# main.net
KiCad netlist of a schematic drawn in Altium Designer
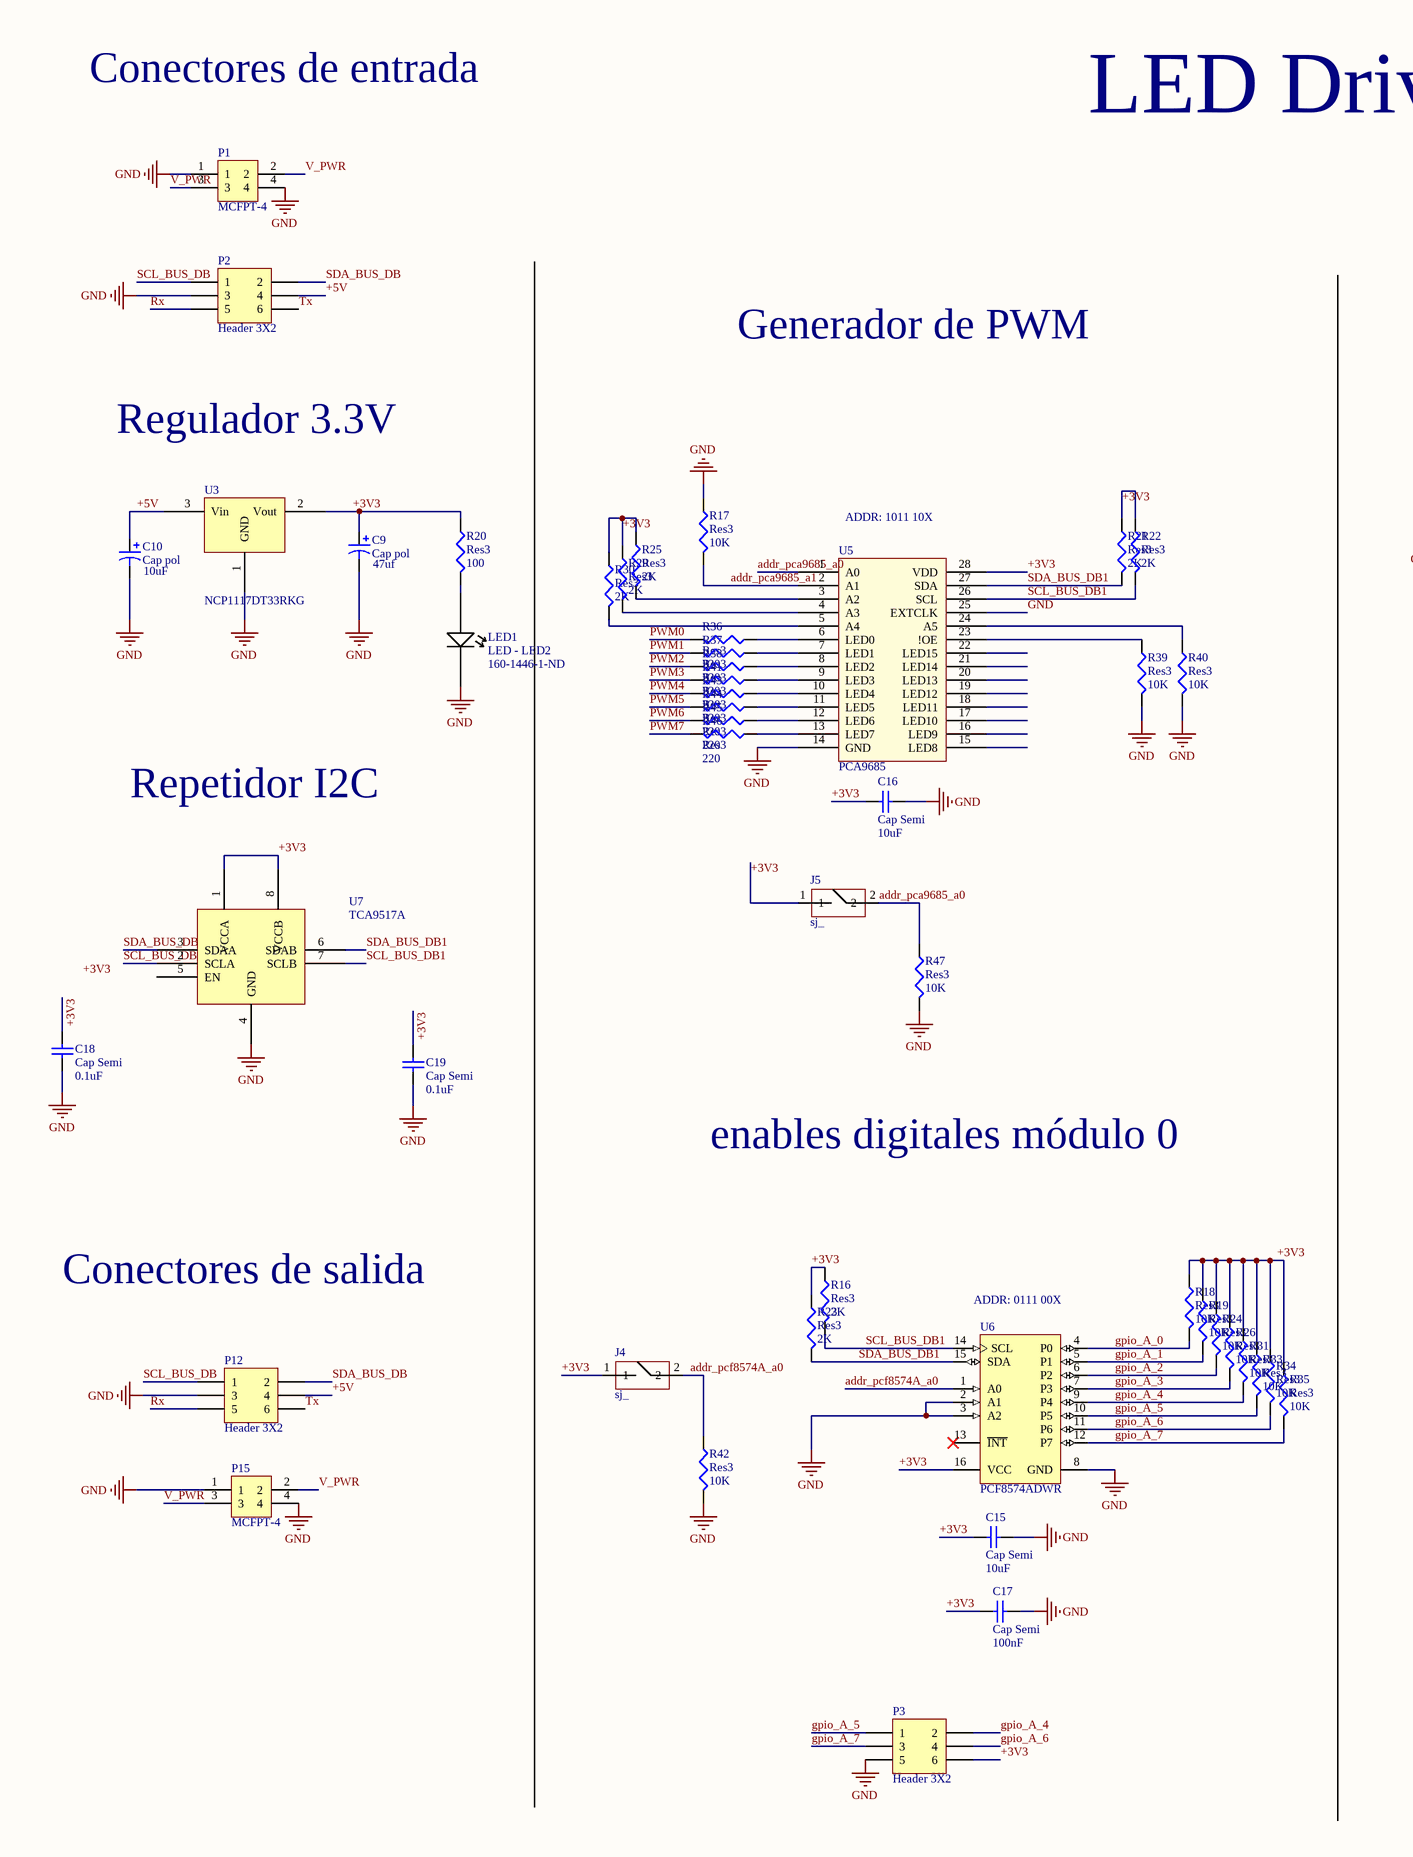
[diagram p0: main.SchDoc, left]
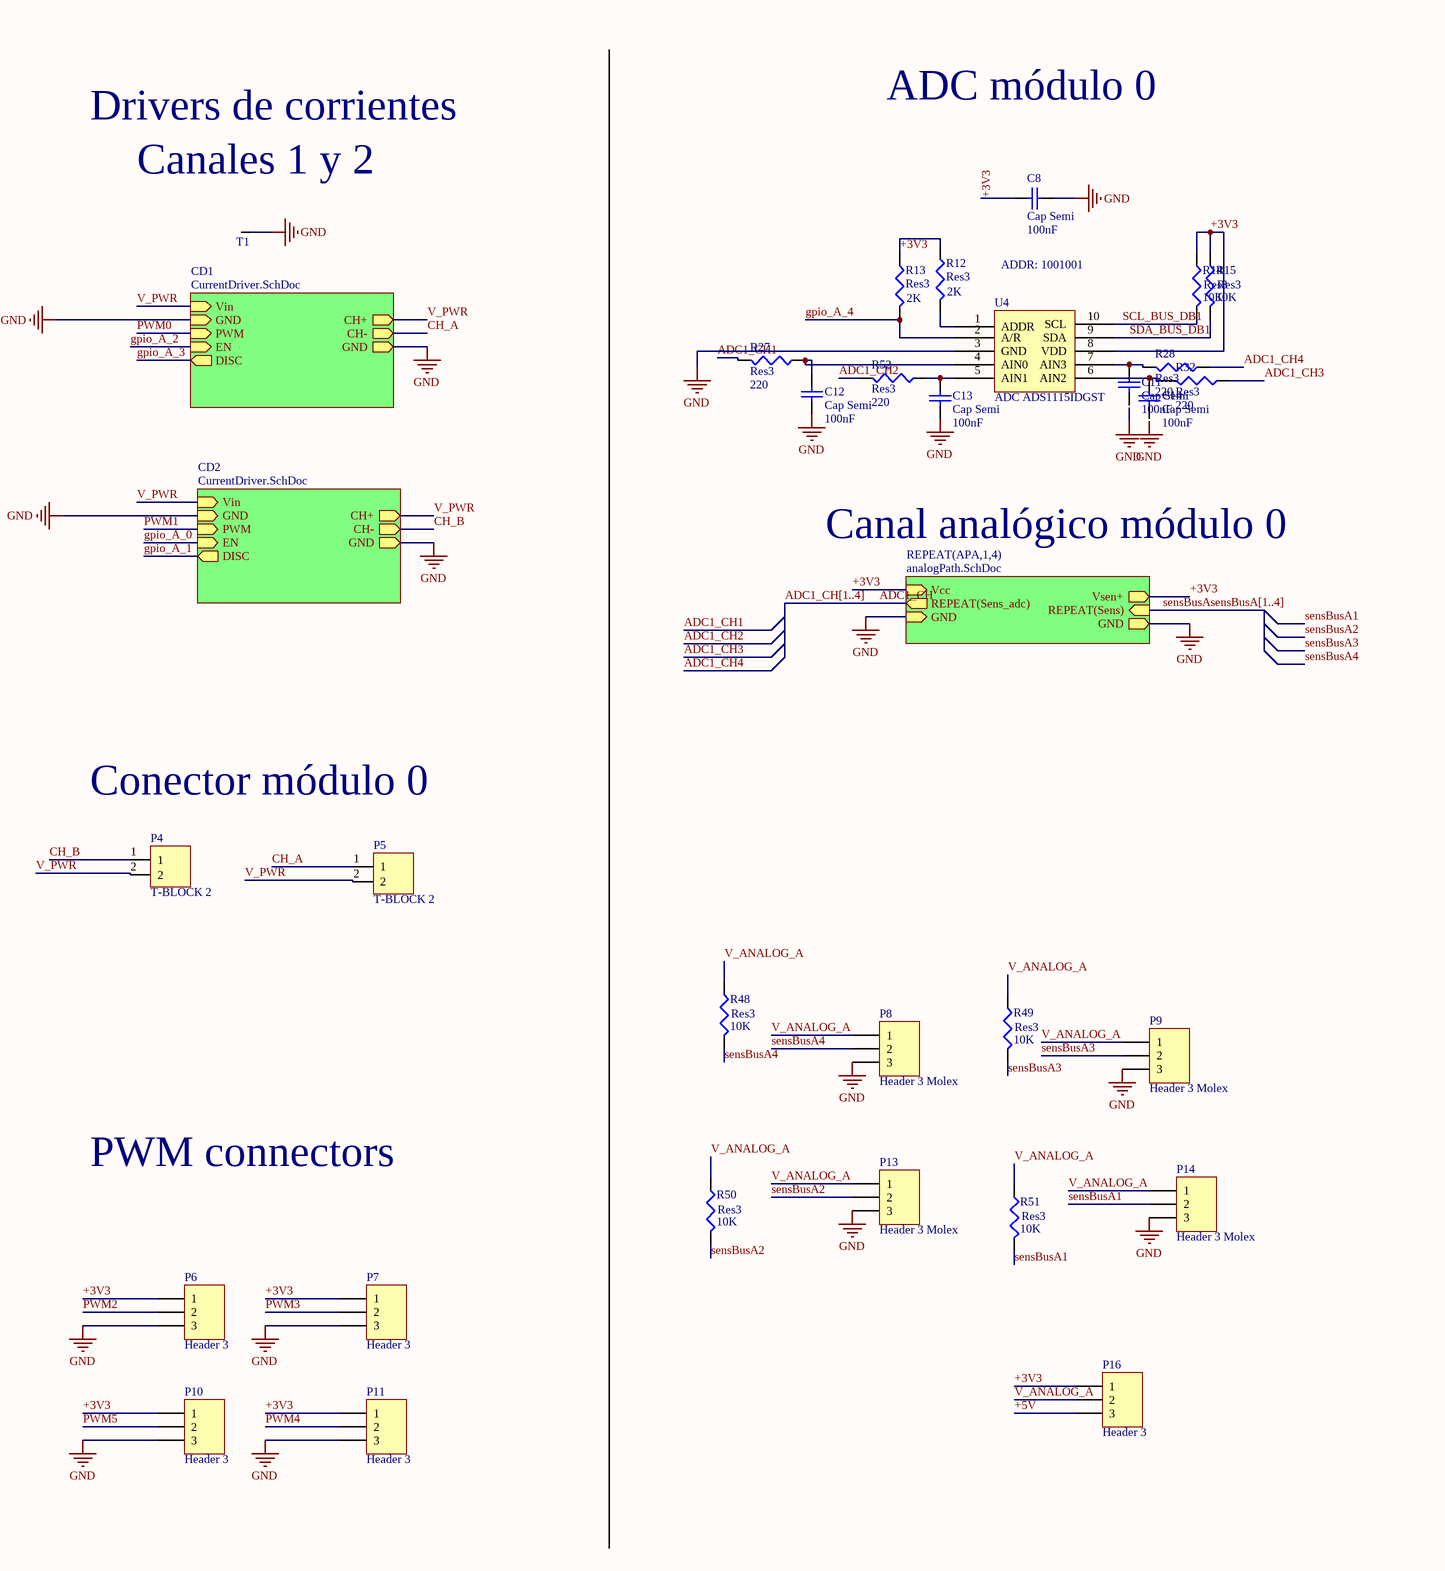
[diagram p1: main.SchDoc, right]

(export (version "E")
  (design (tool "Eeschema 10.0.6"))
  (components
    (comp (ref "C8")
      (value "Cap Semi")
      (footprint "1608[0603]")
      (description "Capacitor (Semiconductor SIM Model)")
      (fields (field (name "ALTIUM_VALUE") "100nF") (field (name "PUBLISHER") "Altium Limited"))
      (libsource (lib "Miscellaneous Devices") (part "Cap Semi"))
    )
    (comp (ref "C9")
      (value "Cap pol")
      (footprint "CAPEA-5.30x5.30")
      (description "Cap Generic")
      (fields (field (name "ALTIUM_VALUE") "47uf"))
      (libsource (lib "ASI-LIB") (part "Cap pol generic"))
    )
    (comp (ref "C10")
      (value "Cap pol")
      (footprint "CAPEA-4.30x4.30")
      (description "Cap Generic")
      (fields (field (name "ALTIUM_VALUE") "10uF"))
      (libsource (lib "ASI-LIB") (part "Cap pol generic"))
    )
    (comp (ref "C11")
      (value "Cap Semi")
      (footprint "1608[0603]")
      (description "Capacitor (Semiconductor SIM Model)")
      (fields (field (name "ALTIUM_VALUE") "100nF") (field (name "PUBLISHER") "Altium Limited"))
      (libsource (lib "Miscellaneous Devices") (part "Cap Semi"))
    )
    (comp (ref "C12")
      (value "Cap Semi")
      (footprint "1608[0603]")
      (description "Capacitor (Semiconductor SIM Model)")
      (fields (field (name "ALTIUM_VALUE") "100nF") (field (name "PUBLISHER") "Altium Limited"))
      (libsource (lib "Miscellaneous Devices") (part "Cap Semi"))
    )
    (comp (ref "C13")
      (value "Cap Semi")
      (footprint "1608[0603]")
      (description "Capacitor (Semiconductor SIM Model)")
      (fields (field (name "ALTIUM_VALUE") "100nF") (field (name "PUBLISHER") "Altium Limited"))
      (libsource (lib "Miscellaneous Devices") (part "Cap Semi"))
    )
    (comp (ref "C14")
      (value "Cap Semi")
      (footprint "1608[0603]")
      (description "Capacitor (Semiconductor SIM Model)")
      (fields (field (name "ALTIUM_VALUE") "100nF") (field (name "PUBLISHER") "Altium Limited"))
      (libsource (lib "Miscellaneous Devices") (part "Cap Semi"))
    )
    (comp (ref "C15")
      (value "Cap Semi")
      (footprint "1608[0603]")
      (description "Capacitor (Semiconductor SIM Model)")
      (fields (field (name "ALTIUM_VALUE") "10uF") (field (name "PUBLISHER") "Altium Limited"))
      (libsource (lib "Miscellaneous Devices") (part "Cap Semi"))
    )
    (comp (ref "C16")
      (value "Cap Semi")
      (footprint "1608[0603]")
      (description "Capacitor (Semiconductor SIM Model)")
      (fields (field (name "ALTIUM_VALUE") "10uF") (field (name "PUBLISHER") "Altium Limited"))
      (libsource (lib "Miscellaneous Devices") (part "Cap Semi"))
    )
    (comp (ref "C17")
      (value "Cap Semi")
      (footprint "1608[0603]")
      (description "Capacitor (Semiconductor SIM Model)")
      (fields (field (name "ALTIUM_VALUE") "100nF") (field (name "PUBLISHER") "Altium Limited"))
      (libsource (lib "Miscellaneous Devices") (part "Cap Semi"))
    )
    (comp (ref "C18")
      (value "Cap Semi")
      (footprint "1608[0603]")
      (description "Capacitor (Semiconductor SIM Model)")
      (fields (field (name "ALTIUM_VALUE") "0.1uF") (field (name "PUBLISHER") "Altium Limited"))
      (libsource (lib "Miscellaneous Devices") (part "Cap Semi"))
    )
    (comp (ref "C19")
      (value "Cap Semi")
      (footprint "1608[0603]")
      (description "Capacitor (Semiconductor SIM Model)")
      (fields (field (name "ALTIUM_VALUE") "0.1uF") (field (name "PUBLISHER") "Altium Limited"))
      (libsource (lib "Miscellaneous Devices") (part "Cap Semi"))
    )
    (comp (ref "J4")
      (value "sj_")
      (footprint "JUMPER_NET_TIE")
      (description "solder jumper generic")
      (libsource (lib "ASI-LIB") (part "Jumper"))
    )
    (comp (ref "J5")
      (value "sj_")
      (footprint "JUMPER_NET_TIE")
      (description "solder jumper generic")
      (libsource (lib "ASI-LIB") (part "Jumper"))
    )
    (comp (ref "LED1")
      (value "LED - LED2")
      (footprint "LED")
      (fields (field (name "SUPPLIER PART NUMBER 1") "160-1446-1-ND"))
      (libsource (lib "ASI-LIB") (part "LED - LED2"))
    )
    (comp (ref "P1")
      (value "MCFPT-4")
      (footprint "MCFPT-4-VERT")
      (description "POWER CONN")
      (libsource (lib "ASI-LIB") (part "CON - MCFPT-4"))
    )
    (comp (ref "P2")
      (value "Header 3X2")
      (footprint "HDR2X3")
      (description "Header, 3-Pin, Dual row")
      (fields (field (name "PUBLISHER") "Altium Limited"))
      (libsource (lib "Miscellaneous Connectors") (part "Header 3X2"))
    )
    (comp (ref "P3")
      (value "Header 3X2")
      (footprint "HDR2X3")
      (description "Header, 3-Pin, Dual row")
      (fields (field (name "PUBLISHER") "Altium Limited"))
      (libsource (lib "Miscellaneous Connectors") (part "Header 3X2"))
    )
    (comp (ref "P4")
      (value "T-BLOCK 2")
      (footprint "T-BLOCK_2_3MM")
      (description "TE Connectivity Buchanan Series 3.5mm Pitch Straight, PCB Terminal Block, Through Hole, 2 Way")
      (libsource (lib "ASI-LIB") (part "T-BLOCK_2_3MM"))
    )
    (comp (ref "P5")
      (value "T-BLOCK 2")
      (footprint "T-BLOCK_2_3MM")
      (description "TE Connectivity Buchanan Series 3.5mm Pitch Straight, PCB Terminal Block, Through Hole, 2 Way")
      (libsource (lib "ASI-LIB") (part "T-BLOCK_2_3MM"))
    )
    (comp (ref "P6")
      (value "Header 3")
      (footprint "HDR1X3")
      (description "Header, 3-Pin")
      (fields (field (name "PUBLISHER") "Altium Limited"))
      (libsource (lib "Miscellaneous Connectors") (part "Header 3"))
    )
    (comp (ref "P7")
      (value "Header 3")
      (footprint "HDR1X3")
      (description "Header, 3-Pin")
      (fields (field (name "PUBLISHER") "Altium Limited"))
      (libsource (lib "Miscellaneous Connectors") (part "Header 3"))
    )
    (comp (ref "P8")
      (value "Header 3 Molex")
      (footprint "HDR1X3")
      (description "Header, 3-Pin")
      (fields (field (name "GENERIC PART NUMBER") "22272031") (field (name "PUBLISHER") "Altium Limited"))
      (libsource (lib "ASI-LIB") (part "Header 3 Molex"))
    )
    (comp (ref "P9")
      (value "Header 3 Molex")
      (footprint "HDR1X3")
      (description "Header, 3-Pin")
      (fields (field (name "GENERIC PART NUMBER") "22272031") (field (name "PUBLISHER") "Altium Limited"))
      (libsource (lib "ASI-LIB") (part "Header 3 Molex"))
    )
    (comp (ref "P10")
      (value "Header 3")
      (footprint "HDR1X3")
      (description "Header, 3-Pin")
      (fields (field (name "PUBLISHER") "Altium Limited"))
      (libsource (lib "Miscellaneous Connectors") (part "Header 3"))
    )
    (comp (ref "P11")
      (value "Header 3")
      (footprint "HDR1X3")
      (description "Header, 3-Pin")
      (fields (field (name "PUBLISHER") "Altium Limited"))
      (libsource (lib "Miscellaneous Connectors") (part "Header 3"))
    )
    (comp (ref "P12")
      (value "Header 3X2")
      (footprint "HDR2X3")
      (description "Header, 3-Pin, Dual row")
      (fields (field (name "PUBLISHER") "Altium Limited"))
      (libsource (lib "Miscellaneous Connectors") (part "Header 3X2"))
    )
    (comp (ref "P13")
      (value "Header 3 Molex")
      (footprint "HDR1X3")
      (description "Header, 3-Pin")
      (fields (field (name "GENERIC PART NUMBER") "22272031") (field (name "PUBLISHER") "Altium Limited"))
      (libsource (lib "ASI-LIB") (part "Header 3 Molex"))
    )
    (comp (ref "P14")
      (value "Header 3 Molex")
      (footprint "HDR1X3")
      (description "Header, 3-Pin")
      (fields (field (name "GENERIC PART NUMBER") "22272031") (field (name "PUBLISHER") "Altium Limited"))
      (libsource (lib "ASI-LIB") (part "Header 3 Molex"))
    )
    (comp (ref "P15")
      (value "MCFPT-4")
      (footprint "MCFPT-4-VERT")
      (description "POWER CONN")
      (libsource (lib "ASI-LIB") (part "CON - MCFPT-4"))
    )
    (comp (ref "P16")
      (value "Header 3")
      (footprint "HDR1X3")
      (description "Header, 3-Pin")
      (fields (field (name "PUBLISHER") "Altium Limited"))
      (libsource (lib "Miscellaneous Connectors") (part "Header 3"))
    )
    (comp (ref "R12")
      (value "Res3")
      (footprint "J1-0603")
      (description "Resistor")
      (fields (field (name "ALTIUM_VALUE") "2K") (field (name "PUBLISHER") "Altium Limited"))
      (libsource (lib "Miscellaneous Devices") (part "Res3"))
    )
    (comp (ref "R13")
      (value "Res3")
      (footprint "J1-0603")
      (description "Resistor")
      (fields (field (name "ALTIUM_VALUE") "2K") (field (name "PUBLISHER") "Altium Limited"))
      (libsource (lib "Miscellaneous Devices") (part "Res3"))
    )
    (comp (ref "R14")
      (value "Res3")
      (footprint "J1-0603")
      (description "Resistor")
      (fields (field (name "ALTIUM_VALUE") "10K") (field (name "PUBLISHER") "Altium Limited"))
      (libsource (lib "Miscellaneous Devices") (part "Res3"))
    )
    (comp (ref "R15")
      (value "Res3")
      (footprint "J1-0603")
      (description "Resistor")
      (fields (field (name "ALTIUM_VALUE") "10K") (field (name "PUBLISHER") "Altium Limited"))
      (libsource (lib "Miscellaneous Devices") (part "Res3"))
    )
    (comp (ref "R16")
      (value "Res3")
      (footprint "J1-0603")
      (description "Resistor")
      (fields (field (name "ALTIUM_VALUE") "2K") (field (name "PUBLISHER") "Altium Limited"))
      (libsource (lib "Miscellaneous Devices") (part "Res3"))
    )
    (comp (ref "R17")
      (value "Res3")
      (footprint "J1-0603")
      (description "Resistor")
      (fields (field (name "ALTIUM_VALUE") "10K") (field (name "PUBLISHER") "Altium Limited"))
      (libsource (lib "Miscellaneous Devices") (part "Res3"))
    )
    (comp (ref "R18")
      (value "Res3")
      (footprint "J1-0603")
      (description "Resistor")
      (fields (field (name "ALTIUM_VALUE") "10K") (field (name "PUBLISHER") "Altium Limited"))
      (libsource (lib "Miscellaneous Devices") (part "Res3"))
    )
    (comp (ref "R19")
      (value "Res3")
      (footprint "J1-0603")
      (description "Resistor")
      (fields (field (name "ALTIUM_VALUE") "10K") (field (name "PUBLISHER") "Altium Limited"))
      (libsource (lib "Miscellaneous Devices") (part "Res3"))
    )
    (comp (ref "R20")
      (value "Res3")
      (footprint "J1-0603")
      (description "Resistor")
      (fields (field (name "ALTIUM_VALUE") "100") (field (name "PUBLISHER") "Altium Limited"))
      (libsource (lib "Miscellaneous Devices") (part "Res3"))
    )
    (comp (ref "R21")
      (value "Res3")
      (footprint "J1-0603")
      (description "Resistor")
      (fields (field (name "ALTIUM_VALUE") "2K") (field (name "PUBLISHER") "Altium Limited"))
      (libsource (lib "Miscellaneous Devices") (part "Res3"))
    )
    (comp (ref "R22")
      (value "Res3")
      (footprint "J1-0603")
      (description "Resistor")
      (fields (field (name "ALTIUM_VALUE") "2K") (field (name "PUBLISHER") "Altium Limited"))
      (libsource (lib "Miscellaneous Devices") (part "Res3"))
    )
    (comp (ref "R23")
      (value "Res3")
      (footprint "J1-0603")
      (description "Resistor")
      (fields (field (name "ALTIUM_VALUE") "2K") (field (name "PUBLISHER") "Altium Limited"))
      (libsource (lib "Miscellaneous Devices") (part "Res3"))
    )
    (comp (ref "R24")
      (value "Res3")
      (footprint "J1-0603")
      (description "Resistor")
      (fields (field (name "ALTIUM_VALUE") "10K") (field (name "PUBLISHER") "Altium Limited"))
      (libsource (lib "Miscellaneous Devices") (part "Res3"))
    )
    (comp (ref "R25")
      (value "Res3")
      (footprint "J1-0603")
      (description "Resistor")
      (fields (field (name "ALTIUM_VALUE") "2K") (field (name "PUBLISHER") "Altium Limited"))
      (libsource (lib "Miscellaneous Devices") (part "Res3"))
    )
    (comp (ref "R26")
      (value "Res3")
      (footprint "J1-0603")
      (description "Resistor")
      (fields (field (name "ALTIUM_VALUE") "10K") (field (name "PUBLISHER") "Altium Limited"))
      (libsource (lib "Miscellaneous Devices") (part "Res3"))
    )
    (comp (ref "R27")
      (value "Res3")
      (footprint "J1-0603")
      (description "Resistor")
      (fields (field (name "ALTIUM_VALUE") "220") (field (name "PUBLISHER") "Altium Limited"))
      (libsource (lib "Miscellaneous Devices") (part "Res3"))
    )
    (comp (ref "R28")
      (value "Res3")
      (footprint "J1-0603")
      (description "Resistor")
      (fields (field (name "ALTIUM_VALUE") "220") (field (name "PUBLISHER") "Altium Limited"))
      (libsource (lib "Miscellaneous Devices") (part "Res3"))
    )
    (comp (ref "R29")
      (value "Res3")
      (footprint "J1-0603")
      (description "Resistor")
      (fields (field (name "ALTIUM_VALUE") "2K") (field (name "PUBLISHER") "Altium Limited"))
      (libsource (lib "Miscellaneous Devices") (part "Res3"))
    )
    (comp (ref "R30")
      (value "Res3")
      (footprint "J1-0603")
      (description "Resistor")
      (fields (field (name "ALTIUM_VALUE") "2K") (field (name "PUBLISHER") "Altium Limited"))
      (libsource (lib "Miscellaneous Devices") (part "Res3"))
    )
    (comp (ref "R31")
      (value "Res3")
      (footprint "J1-0603")
      (description "Resistor")
      (fields (field (name "ALTIUM_VALUE") "10K") (field (name "PUBLISHER") "Altium Limited"))
      (libsource (lib "Miscellaneous Devices") (part "Res3"))
    )
    (comp (ref "R32")
      (value "Res3")
      (footprint "J1-0603")
      (description "Resistor")
      (fields (field (name "ALTIUM_VALUE") "220") (field (name "PUBLISHER") "Altium Limited"))
      (libsource (lib "Miscellaneous Devices") (part "Res3"))
    )
    (comp (ref "R33")
      (value "Res3")
      (footprint "J1-0603")
      (description "Resistor")
      (fields (field (name "ALTIUM_VALUE") "10K") (field (name "PUBLISHER") "Altium Limited"))
      (libsource (lib "Miscellaneous Devices") (part "Res3"))
    )
    (comp (ref "R34")
      (value "Res3")
      (footprint "J1-0603")
      (description "Resistor")
      (fields (field (name "ALTIUM_VALUE") "10K") (field (name "PUBLISHER") "Altium Limited"))
      (libsource (lib "Miscellaneous Devices") (part "Res3"))
    )
    (comp (ref "R35")
      (value "Res3")
      (footprint "J1-0603")
      (description "Resistor")
      (fields (field (name "ALTIUM_VALUE") "10K") (field (name "PUBLISHER") "Altium Limited"))
      (libsource (lib "Miscellaneous Devices") (part "Res3"))
    )
    (comp (ref "R36")
      (value "Res3")
      (footprint "J1-0603")
      (description "Resistor")
      (fields (field (name "ALTIUM_VALUE") "220") (field (name "PUBLISHER") "Altium Limited"))
      (libsource (lib "Miscellaneous Devices") (part "Res3"))
    )
    (comp (ref "R37")
      (value "Res3")
      (footprint "J1-0603")
      (description "Resistor")
      (fields (field (name "ALTIUM_VALUE") "220") (field (name "PUBLISHER") "Altium Limited"))
      (libsource (lib "Miscellaneous Devices") (part "Res3"))
    )
    (comp (ref "R38")
      (value "Res3")
      (footprint "J1-0603")
      (description "Resistor")
      (fields (field (name "ALTIUM_VALUE") "220") (field (name "PUBLISHER") "Altium Limited"))
      (libsource (lib "Miscellaneous Devices") (part "Res3"))
    )
    (comp (ref "R39")
      (value "Res3")
      (footprint "J1-0603")
      (description "Resistor")
      (fields (field (name "ALTIUM_VALUE") "10K") (field (name "PUBLISHER") "Altium Limited"))
      (libsource (lib "Miscellaneous Devices") (part "Res3"))
    )
    (comp (ref "R40")
      (value "Res3")
      (footprint "J1-0603")
      (description "Resistor")
      (fields (field (name "ALTIUM_VALUE") "10K") (field (name "PUBLISHER") "Altium Limited"))
      (libsource (lib "Miscellaneous Devices") (part "Res3"))
    )
    (comp (ref "R41")
      (value "Res3")
      (footprint "J1-0603")
      (description "Resistor")
      (fields (field (name "ALTIUM_VALUE") "220") (field (name "PUBLISHER") "Altium Limited"))
      (libsource (lib "Miscellaneous Devices") (part "Res3"))
    )
    (comp (ref "R42")
      (value "Res3")
      (footprint "J1-0603")
      (description "Resistor")
      (fields (field (name "ALTIUM_VALUE") "10K") (field (name "PUBLISHER") "Altium Limited"))
      (libsource (lib "Miscellaneous Devices") (part "Res3"))
    )
    (comp (ref "R43")
      (value "Res3")
      (footprint "J1-0603")
      (description "Resistor")
      (fields (field (name "ALTIUM_VALUE") "220") (field (name "PUBLISHER") "Altium Limited"))
      (libsource (lib "Miscellaneous Devices") (part "Res3"))
    )
    (comp (ref "R44")
      (value "Res3")
      (footprint "J1-0603")
      (description "Resistor")
      (fields (field (name "ALTIUM_VALUE") "220") (field (name "PUBLISHER") "Altium Limited"))
      (libsource (lib "Miscellaneous Devices") (part "Res3"))
    )
    (comp (ref "R45")
      (value "Res3")
      (footprint "J1-0603")
      (description "Resistor")
      (fields (field (name "ALTIUM_VALUE") "220") (field (name "PUBLISHER") "Altium Limited"))
      (libsource (lib "Miscellaneous Devices") (part "Res3"))
    )
    (comp (ref "R46")
      (value "Res3")
      (footprint "J1-0603")
      (description "Resistor")
      (fields (field (name "ALTIUM_VALUE") "220") (field (name "PUBLISHER") "Altium Limited"))
      (libsource (lib "Miscellaneous Devices") (part "Res3"))
    )
    (comp (ref "R47")
      (value "Res3")
      (footprint "J1-0603")
      (description "Resistor")
      (fields (field (name "ALTIUM_VALUE") "10K") (field (name "PUBLISHER") "Altium Limited"))
      (libsource (lib "Miscellaneous Devices") (part "Res3"))
    )
    (comp (ref "R48")
      (value "Res3")
      (footprint "J1-0603")
      (description "Resistor")
      (fields (field (name "ALTIUM_VALUE") "10K") (field (name "PUBLISHER") "Altium Limited"))
      (libsource (lib "Miscellaneous Devices") (part "Res3"))
    )
    (comp (ref "R49")
      (value "Res3")
      (footprint "J1-0603")
      (description "Resistor")
      (fields (field (name "ALTIUM_VALUE") "10K") (field (name "PUBLISHER") "Altium Limited"))
      (libsource (lib "Miscellaneous Devices") (part "Res3"))
    )
    (comp (ref "R50")
      (value "Res3")
      (footprint "J1-0603")
      (description "Resistor")
      (fields (field (name "ALTIUM_VALUE") "10K") (field (name "PUBLISHER") "Altium Limited"))
      (libsource (lib "Miscellaneous Devices") (part "Res3"))
    )
    (comp (ref "R51")
      (value "Res3")
      (footprint "J1-0603")
      (description "Resistor")
      (fields (field (name "ALTIUM_VALUE") "10K") (field (name "PUBLISHER") "Altium Limited"))
      (libsource (lib "Miscellaneous Devices") (part "Res3"))
    )
    (comp (ref "R52")
      (value "Res3")
      (footprint "J1-0603")
      (description "Resistor")
      (fields (field (name "ALTIUM_VALUE") "220") (field (name "PUBLISHER") "Altium Limited"))
      (libsource (lib "Miscellaneous Devices") (part "Res3"))
    )
    (comp (ref "T1")
      (value "TP - SMALL TP_1")
      (footprint "EXPOSED PAD")
      (description "Test Point")
      (libsource (lib "ASI-LIB") (part "TP - SMALL TP_1"))
    )
    (comp (ref "U3")
      (value "NCP1117DT33RKG")
      (footprint "DPAK")
      (description "Reg npc 1117 3.3 1A DPAk")
      (libsource (lib "ASI-LIB") (part "REG - NPC1117"))
    )
    (comp (ref "U4")
      (value "ADC ADS1115IDGST")
      (footprint "DGS10-L")
      (description "ADC 16bits 4 channels")
      (libsource (lib "ASI-LIB") (part "ADC - ADS1115"))
    )
    (comp (ref "U5")
      (value "PCA9685")
      (footprint "SSOP-28_L")
      (description "16CHANNELS PWM DIM LED DRIVER I2C")
      (libsource (lib "ASI-LIB") (part "PCA9685"))
    )
    (comp (ref "U6")
      (value "PCF8574ADWR")
      (footprint "DW16_N")
      (fields (field (name "MANUFACTURER") "Texas Instruments"))
      (libsource (lib "Texas Instruments Interface I2C") (part "PCF8574ADWR"))
    )
    (comp (ref "U7")
      (value "TCA9517A")
      (footprint "vssop-8")
      (description "I2C BUS REPEATER")
      (libsource (lib "ASI-LIB") (part "TCA9517A"))
    )
  )
  (nets
    (net (code "1") (name "/+3V3") (class "Default")
      (node (ref "C15") (pin "2") (pinfunction "2_2") (pintype "passive"))
      (node (ref "C16") (pin "2") (pinfunction "2_2") (pintype "passive"))
      (node (ref "C17") (pin "2") (pinfunction "2_2") (pintype "passive"))
      (node (ref "C18") (pin "2") (pinfunction "2_2") (pintype "passive"))
      (node (ref "C19") (pin "2") (pinfunction "2_2") (pintype "passive"))
      (node (ref "C8") (pin "2") (pinfunction "2_2") (pintype "passive"))
      (node (ref "C9") (pin "1") (pinfunction "1_1") (pintype "passive"))
      (node (ref "J4") (pin "1") (pinfunction "1_1") (pintype "passive"))
      (node (ref "J5") (pin "1") (pinfunction "1_1") (pintype "passive"))
      (node (ref "P10") (pin "1") (pinfunction "1_1") (pintype "passive"))
      (node (ref "P11") (pin "1") (pinfunction "1_1") (pintype "passive"))
      (node (ref "P16") (pin "1") (pinfunction "1_1") (pintype "passive"))
      (node (ref "P3") (pin "6") (pinfunction "6_6") (pintype "passive"))
      (node (ref "P6") (pin "1") (pinfunction "1_1") (pintype "passive"))
      (node (ref "P7") (pin "1") (pinfunction "1_1") (pintype "passive"))
      (node (ref "R12") (pin "1") (pinfunction "1_1") (pintype "passive"))
      (node (ref "R13") (pin "1") (pinfunction "1_1") (pintype "passive"))
      (node (ref "R14") (pin "2") (pinfunction "2_2") (pintype "passive"))
      (node (ref "R15") (pin "2") (pinfunction "2_2") (pintype "passive"))
      (node (ref "R16") (pin "1") (pinfunction "1_1") (pintype "passive"))
      (node (ref "R18") (pin "2") (pinfunction "2_2") (pintype "passive"))
      (node (ref "R19") (pin "2") (pinfunction "2_2") (pintype "passive"))
      (node (ref "R20") (pin "2") (pinfunction "2_2") (pintype "passive"))
      (node (ref "R21") (pin "1") (pinfunction "1_1") (pintype "passive"))
      (node (ref "R22") (pin "1") (pinfunction "1_1") (pintype "passive"))
      (node (ref "R23") (pin "1") (pinfunction "1_1") (pintype "passive"))
      (node (ref "R24") (pin "2") (pinfunction "2_2") (pintype "passive"))
      (node (ref "R25") (pin "1") (pinfunction "1_1") (pintype "passive"))
      (node (ref "R26") (pin "2") (pinfunction "2_2") (pintype "passive"))
      (node (ref "R29") (pin "1") (pinfunction "1_1") (pintype "passive"))
      (node (ref "R30") (pin "1") (pinfunction "1_1") (pintype "passive"))
      (node (ref "R31") (pin "2") (pinfunction "2_2") (pintype "passive"))
      (node (ref "R33") (pin "2") (pinfunction "2_2") (pintype "passive"))
      (node (ref "R34") (pin "2") (pinfunction "2_2") (pintype "passive"))
      (node (ref "R35") (pin "2") (pinfunction "2_2") (pintype "passive"))
      (node (ref "U3") (pin "2") (pinfunction "Vout_2") (pintype "passive"))
      (node (ref "U4") (pin "8") (pinfunction "VDD_8") (pintype "passive"))
      (node (ref "U5") (pin "28") (pinfunction "VDD_28") (pintype "passive"))
      (node (ref "U6") (pin "16") (pinfunction "VCC_16") (pintype "power_in"))
      (node (ref "U7") (pin "1") (pinfunction "VCCA_1") (pintype "passive"))
      (node (ref "U7") (pin "8") (pinfunction "VCCB_8") (pintype "passive"))
    )
    (net (code "2") (name "/+5V") (class "Default")
      (node (ref "C10") (pin "1") (pinfunction "1_1") (pintype "passive"))
      (node (ref "P12") (pin "4") (pinfunction "4_4") (pintype "passive"))
      (node (ref "P16") (pin "3") (pinfunction "3_3") (pintype "passive"))
      (node (ref "P2") (pin "4") (pinfunction "4_4") (pintype "passive"))
      (node (ref "U3") (pin "3") (pinfunction "Vin_3") (pintype "passive"))
    )
    (net (code "4") (name "/ADC1_CH1") (class "Default")
      (node (ref "R27") (pin "2") (pinfunction "2_2") (pintype "passive"))
    )
    (net (code "5") (name "/ADC1_CH2") (class "Default")
      (node (ref "R52") (pin "2") (pinfunction "2_2") (pintype "passive"))
    )
    (net (code "6") (name "/ADC1_CH3") (class "Default")
      (node (ref "R32") (pin "1") (pinfunction "1_1") (pintype "passive"))
    )
    (net (code "7") (name "/ADC1_CH4") (class "Default")
      (node (ref "R28") (pin "1") (pinfunction "1_1") (pintype "passive"))
    )
    (net (code "9") (name "/CH_A") (class "Default")
      (node (ref "P5") (pin "1") (pinfunction "1_1") (pintype "passive"))
    )
    (net (code "10") (name "/CH_B") (class "Default")
      (node (ref "P4") (pin "1") (pinfunction "1_1") (pintype "passive"))
    )
    (net (code "11") (name "/PWM0") (class "Default")
      (node (ref "R36") (pin "2") (pinfunction "2_2") (pintype "passive"))
    )
    (net (code "12") (name "/PWM1") (class "Default")
      (node (ref "R37") (pin "2") (pinfunction "2_2") (pintype "passive"))
    )
    (net (code "13") (name "/PWM2") (class "Default")
      (node (ref "P6") (pin "2") (pinfunction "2_2") (pintype "passive"))
      (node (ref "R38") (pin "2") (pinfunction "2_2") (pintype "passive"))
    )
    (net (code "14") (name "/PWM3") (class "Default")
      (node (ref "P7") (pin "2") (pinfunction "2_2") (pintype "passive"))
      (node (ref "R41") (pin "2") (pinfunction "2_2") (pintype "passive"))
    )
    (net (code "15") (name "/PWM4") (class "Default")
      (node (ref "P11") (pin "2") (pinfunction "2_2") (pintype "passive"))
      (node (ref "R43") (pin "2") (pinfunction "2_2") (pintype "passive"))
    )
    (net (code "16") (name "/PWM5") (class "Default")
      (node (ref "P10") (pin "2") (pinfunction "2_2") (pintype "passive"))
      (node (ref "R44") (pin "2") (pinfunction "2_2") (pintype "passive"))
    )
    (net (code "17") (name "/PWM6") (class "Default")
      (node (ref "R45") (pin "2") (pinfunction "2_2") (pintype "passive"))
    )
    (net (code "18") (name "/PWM7") (class "Default")
      (node (ref "R46") (pin "2") (pinfunction "2_2") (pintype "passive"))
    )
    (net (code "19") (name "/Rx") (class "Default")
      (node (ref "P12") (pin "5") (pinfunction "5_5") (pintype "passive"))
      (node (ref "P2") (pin "5") (pinfunction "5_5") (pintype "passive"))
    )
    (net (code "20") (name "/SCL_BUS_DB") (class "Default")
      (node (ref "P12") (pin "1") (pinfunction "1_1") (pintype "passive"))
      (node (ref "P2") (pin "1") (pinfunction "1_1") (pintype "passive"))
      (node (ref "U7") (pin "2") (pinfunction "SCLA_2") (pintype "passive"))
    )
    (net (code "21") (name "/SCL_BUS_DB1") (class "Default")
      (node (ref "R14") (pin "1") (pinfunction "1_1") (pintype "passive"))
      (node (ref "R16") (pin "2") (pinfunction "2_2") (pintype "passive"))
      (node (ref "R22") (pin "2") (pinfunction "2_2") (pintype "passive"))
      (node (ref "U4") (pin "10") (pinfunction "SCL_10") (pintype "passive"))
      (node (ref "U5") (pin "26") (pinfunction "SCL_26") (pintype "passive"))
      (node (ref "U6") (pin "14") (pinfunction "SCL_14") (pintype "input"))
      (node (ref "U7") (pin "7") (pinfunction "SCLB_7") (pintype "passive"))
    )
    (net (code "22") (name "/SDA_BUS_DB") (class "Default")
      (node (ref "P12") (pin "2") (pinfunction "2_2") (pintype "passive"))
      (node (ref "P2") (pin "2") (pinfunction "2_2") (pintype "passive"))
      (node (ref "U7") (pin "3") (pinfunction "SDAA_3") (pintype "passive"))
    )
    (net (code "23") (name "/SDA_BUS_DB1") (class "Default")
      (node (ref "R15") (pin "1") (pinfunction "1_1") (pintype "passive"))
      (node (ref "R21") (pin "2") (pinfunction "2_2") (pintype "passive"))
      (node (ref "R23") (pin "2") (pinfunction "2_2") (pintype "passive"))
      (node (ref "U4") (pin "9") (pinfunction "SDA_9") (pintype "passive"))
      (node (ref "U5") (pin "27") (pinfunction "SDA_27") (pintype "passive"))
      (node (ref "U6") (pin "15") (pinfunction "SDA_15") (pintype "bidirectional"))
      (node (ref "U7") (pin "6") (pinfunction "SDAB_6") (pintype "passive"))
    )
    (net (code "24") (name "/Tx") (class "Default")
      (node (ref "P12") (pin "6") (pinfunction "6_6") (pintype "passive"))
      (node (ref "P2") (pin "6") (pinfunction "6_6") (pintype "passive"))
    )
    (net (code "25") (name "/V_ANALOG_A") (class "Default")
      (node (ref "P13") (pin "1") (pinfunction "1_1") (pintype "passive"))
      (node (ref "P14") (pin "1") (pinfunction "1_1") (pintype "passive"))
      (node (ref "P16") (pin "2") (pinfunction "2_2") (pintype "passive"))
      (node (ref "P8") (pin "1") (pinfunction "1_1") (pintype "passive"))
      (node (ref "P9") (pin "1") (pinfunction "1_1") (pintype "passive"))
      (node (ref "R48") (pin "2") (pinfunction "2_2") (pintype "passive"))
      (node (ref "R49") (pin "2") (pinfunction "2_2") (pintype "passive"))
      (node (ref "R50") (pin "2") (pinfunction "2_2") (pintype "passive"))
      (node (ref "R51") (pin "2") (pinfunction "2_2") (pintype "passive"))
    )
    (net (code "26") (name "/V_PWR") (class "Default")
      (node (ref "P1") (pin "2") (pinfunction "2_2") (pintype "passive"))
      (node (ref "P1") (pin "3") (pinfunction "3_3") (pintype "passive"))
      (node (ref "P15") (pin "2") (pinfunction "2_2") (pintype "passive"))
      (node (ref "P15") (pin "3") (pinfunction "3_3") (pintype "passive"))
      (node (ref "P4") (pin "2") (pinfunction "2_2") (pintype "passive"))
      (node (ref "P5") (pin "2") (pinfunction "2_2") (pintype "passive"))
    )
    (net (code "27") (name "/addr_pca9685_a0") (class "Default")
      (node (ref "J5") (pin "2") (pinfunction "2_2") (pintype "passive"))
      (node (ref "R47") (pin "2") (pinfunction "2_2") (pintype "passive"))
      (node (ref "U5") (pin "1") (pinfunction "A0_1") (pintype "passive"))
    )
    (net (code "28") (name "/addr_pca9685_a1") (class "Default")
      (node (ref "R17") (pin "1") (pinfunction "1_1") (pintype "passive"))
      (node (ref "U5") (pin "2") (pinfunction "A1_2") (pintype "passive"))
    )
    (net (code "29") (name "/addr_pcf8574A_a0") (class "Default")
      (node (ref "J4") (pin "2") (pinfunction "2_2") (pintype "passive"))
      (node (ref "R42") (pin "2") (pinfunction "2_2") (pintype "passive"))
      (node (ref "U6") (pin "1") (pinfunction "A0_1") (pintype "input"))
    )
    (net (code "30") (name "/gpio_A_0") (class "Default")
      (node (ref "R18") (pin "1") (pinfunction "1_1") (pintype "passive"))
      (node (ref "U6") (pin "4") (pinfunction "P0_4") (pintype "bidirectional"))
    )
    (net (code "31") (name "/gpio_A_1") (class "Default")
      (node (ref "R19") (pin "1") (pinfunction "1_1") (pintype "passive"))
      (node (ref "U6") (pin "5") (pinfunction "P1_5") (pintype "bidirectional"))
    )
    (net (code "32") (name "/gpio_A_2") (class "Default")
      (node (ref "R24") (pin "1") (pinfunction "1_1") (pintype "passive"))
      (node (ref "U6") (pin "6") (pinfunction "P2_6") (pintype "bidirectional"))
    )
    (net (code "33") (name "/gpio_A_3") (class "Default")
      (node (ref "R26") (pin "1") (pinfunction "1_1") (pintype "passive"))
      (node (ref "U6") (pin "7") (pinfunction "P3_7") (pintype "bidirectional"))
    )
    (net (code "34") (name "/gpio_A_4") (class "Default")
      (node (ref "P3") (pin "2") (pinfunction "2_2") (pintype "passive"))
      (node (ref "R13") (pin "2") (pinfunction "2_2") (pintype "passive"))
      (node (ref "R31") (pin "1") (pinfunction "1_1") (pintype "passive"))
      (node (ref "U4") (pin "2") (pinfunction "A/R_2") (pintype "passive"))
      (node (ref "U6") (pin "9") (pinfunction "P4_9") (pintype "bidirectional"))
    )
    (net (code "35") (name "/gpio_A_5") (class "Default")
      (node (ref "P3") (pin "1") (pinfunction "1_1") (pintype "passive"))
      (node (ref "R33") (pin "1") (pinfunction "1_1") (pintype "passive"))
      (node (ref "U6") (pin "10") (pinfunction "P5_10") (pintype "bidirectional"))
    )
    (net (code "36") (name "/gpio_A_6") (class "Default")
      (node (ref "P3") (pin "4") (pinfunction "4_4") (pintype "passive"))
      (node (ref "R34") (pin "1") (pinfunction "1_1") (pintype "passive"))
      (node (ref "U6") (pin "11") (pinfunction "P6_11") (pintype "bidirectional"))
    )
    (net (code "37") (name "/gpio_A_7") (class "Default")
      (node (ref "P3") (pin "3") (pinfunction "3_3") (pintype "passive"))
      (node (ref "R35") (pin "1") (pinfunction "1_1") (pintype "passive"))
      (node (ref "U6") (pin "12") (pinfunction "P7_12") (pintype "bidirectional"))
    )
    (net (code "39") (name "/sensBusA1") (class "Default")
      (node (ref "P14") (pin "2") (pinfunction "2_2") (pintype "passive"))
      (node (ref "R51") (pin "1") (pinfunction "1_1") (pintype "passive"))
    )
    (net (code "40") (name "/sensBusA2") (class "Default")
      (node (ref "P13") (pin "2") (pinfunction "2_2") (pintype "passive"))
      (node (ref "R50") (pin "1") (pinfunction "1_1") (pintype "passive"))
    )
    (net (code "41") (name "/sensBusA3") (class "Default")
      (node (ref "P9") (pin "2") (pinfunction "2_2") (pintype "passive"))
      (node (ref "R49") (pin "1") (pinfunction "1_1") (pintype "passive"))
    )
    (net (code "42") (name "/sensBusA4") (class "Default")
      (node (ref "P8") (pin "2") (pinfunction "2_2") (pintype "passive"))
      (node (ref "R48") (pin "1") (pinfunction "1_1") (pintype "passive"))
    )
    (net (code "43") (name "GND") (class "Default")
      (node (ref "C10") (pin "2") (pinfunction "2_2") (pintype "passive"))
      (node (ref "C12") (pin "2") (pinfunction "2_2") (pintype "passive"))
      (node (ref "C13") (pin "2") (pinfunction "2_2") (pintype "passive"))
      (node (ref "C15") (pin "1") (pinfunction "1_1") (pintype "passive"))
      (node (ref "C16") (pin "1") (pinfunction "1_1") (pintype "passive"))
      (node (ref "C17") (pin "1") (pinfunction "1_1") (pintype "passive"))
      (node (ref "C18") (pin "1") (pinfunction "1_1") (pintype "passive"))
      (node (ref "C19") (pin "1") (pinfunction "1_1") (pintype "passive"))
      (node (ref "C8") (pin "1") (pinfunction "1_1") (pintype "passive"))
      (node (ref "C9") (pin "2") (pinfunction "2_2") (pintype "passive"))
      (node (ref "LED1") (pin "2") (pinfunction "2_2") (pintype "passive"))
      (node (ref "P1") (pin "1") (pinfunction "1_1") (pintype "passive"))
      (node (ref "P1") (pin "4") (pinfunction "4_4") (pintype "passive"))
      (node (ref "P10") (pin "3") (pinfunction "3_3") (pintype "passive"))
      (node (ref "P11") (pin "3") (pinfunction "3_3") (pintype "passive"))
      (node (ref "P12") (pin "3") (pinfunction "3_3") (pintype "passive"))
      (node (ref "P13") (pin "3") (pinfunction "3_3") (pintype "passive"))
      (node (ref "P14") (pin "3") (pinfunction "3_3") (pintype "passive"))
      (node (ref "P15") (pin "1") (pinfunction "1_1") (pintype "passive"))
      (node (ref "P15") (pin "4") (pinfunction "4_4") (pintype "passive"))
      (node (ref "P2") (pin "3") (pinfunction "3_3") (pintype "passive"))
      (node (ref "P3") (pin "5") (pinfunction "5_5") (pintype "passive"))
      (node (ref "P6") (pin "3") (pinfunction "3_3") (pintype "passive"))
      (node (ref "P7") (pin "3") (pinfunction "3_3") (pintype "passive"))
      (node (ref "P8") (pin "3") (pinfunction "3_3") (pintype "passive"))
      (node (ref "P9") (pin "3") (pinfunction "3_3") (pintype "passive"))
      (node (ref "R17") (pin "2") (pinfunction "2_2") (pintype "passive"))
      (node (ref "R39") (pin "1") (pinfunction "1_1") (pintype "passive"))
      (node (ref "R40") (pin "1") (pinfunction "1_1") (pintype "passive"))
      (node (ref "R42") (pin "1") (pinfunction "1_1") (pintype "passive"))
      (node (ref "R47") (pin "1") (pinfunction "1_1") (pintype "passive"))
      (node (ref "T1") (pin "1") (pintype "passive"))
      (node (ref "U3") (pin "1") (pinfunction "GND_1") (pintype "passive"))
      (node (ref "U4") (pin "3") (pinfunction "GND_3") (pintype "passive"))
      (node (ref "U5") (pin "14") (pinfunction "GND_14") (pintype "passive"))
      (node (ref "U5") (pin "25") (pinfunction "EXTCLK_25") (pintype "passive"))
      (node (ref "U6") (pin "2") (pinfunction "A1_2") (pintype "input"))
      (node (ref "U6") (pin "3") (pinfunction "A2_3") (pintype "input"))
      (node (ref "U6") (pin "8") (pinfunction "GND_8") (pintype "power_in"))
      (node (ref "U7") (pin "4") (pinfunction "GND_4") (pintype "passive"))
    )
    (net (code "44") (name "Net-(LED1-Pad1)") (class "Default")
      (node (ref "LED1") (pin "1") (pinfunction "1_1") (pintype "passive"))
      (node (ref "R20") (pin "1") (pinfunction "1_1") (pintype "passive"))
    )
    (net (code "45") (name "Net-(U4-ADDR)") (class "Default")
      (node (ref "R12") (pin "2") (pinfunction "2_2") (pintype "passive"))
      (node (ref "U4") (pin "1") (pinfunction "ADDR_1") (pintype "passive"))
    )
    (net (code "46") (name "Net-(U4-AIN0)") (class "Default")
      (node (ref "C12") (pin "1") (pinfunction "1_1") (pintype "passive"))
      (node (ref "R27") (pin "1") (pinfunction "1_1") (pintype "passive"))
      (node (ref "U4") (pin "4") (pinfunction "AIN0_4") (pintype "passive"))
    )
    (net (code "47") (name "Net-(U4-AIN1)") (class "Default")
      (node (ref "C13") (pin "1") (pinfunction "1_1") (pintype "passive"))
      (node (ref "R52") (pin "1") (pinfunction "1_1") (pintype "passive"))
      (node (ref "U4") (pin "5") (pinfunction "AIN1_5") (pintype "passive"))
    )
    (net (code "48") (name "Net-(U4-AIN2)") (class "Default")
      (node (ref "C14") (pin "1") (pinfunction "1_1") (pintype "passive"))
      (node (ref "R32") (pin "2") (pinfunction "2_2") (pintype "passive"))
      (node (ref "U4") (pin "6") (pinfunction "AIN2_6") (pintype "passive"))
    )
    (net (code "49") (name "Net-(U4-AIN3)") (class "Default")
      (node (ref "C11") (pin "1") (pinfunction "1_1") (pintype "passive"))
      (node (ref "R28") (pin "2") (pinfunction "2_2") (pintype "passive"))
      (node (ref "U4") (pin "7") (pinfunction "AIN3_7") (pintype "passive"))
    )
    (net (code "50") (name "Net-(U5-!OE)") (class "Default")
      (node (ref "R39") (pin "2") (pinfunction "2_2") (pintype "passive"))
      (node (ref "U5") (pin "23") (pinfunction "!OE_23") (pintype "passive"))
    )
    (net (code "51") (name "Net-(U5-A2)") (class "Default")
      (node (ref "R25") (pin "2") (pinfunction "2_2") (pintype "passive"))
      (node (ref "U5") (pin "3") (pinfunction "A2_3") (pintype "passive"))
    )
    (net (code "52") (name "Net-(U5-A3)") (class "Default")
      (node (ref "R29") (pin "2") (pinfunction "2_2") (pintype "passive"))
      (node (ref "U5") (pin "4") (pinfunction "A3_4") (pintype "passive"))
    )
    (net (code "53") (name "Net-(U5-A4)") (class "Default")
      (node (ref "R30") (pin "2") (pinfunction "2_2") (pintype "passive"))
      (node (ref "U5") (pin "5") (pinfunction "A4_5") (pintype "passive"))
    )
    (net (code "54") (name "Net-(U5-A5)") (class "Default")
      (node (ref "R40") (pin "2") (pinfunction "2_2") (pintype "passive"))
      (node (ref "U5") (pin "24") (pinfunction "A5_24") (pintype "passive"))
    )
    (net (code "55") (name "Net-(U5-LED0)") (class "Default")
      (node (ref "R36") (pin "1") (pinfunction "1_1") (pintype "passive"))
      (node (ref "U5") (pin "6") (pinfunction "LED0_6") (pintype "passive"))
    )
    (net (code "56") (name "Net-(U5-LED1)") (class "Default")
      (node (ref "R37") (pin "1") (pinfunction "1_1") (pintype "passive"))
      (node (ref "U5") (pin "7") (pinfunction "LED1_7") (pintype "passive"))
    )
    (net (code "57") (name "Net-(U5-LED2)") (class "Default")
      (node (ref "R38") (pin "1") (pinfunction "1_1") (pintype "passive"))
      (node (ref "U5") (pin "8") (pinfunction "LED2_8") (pintype "passive"))
    )
    (net (code "58") (name "Net-(U5-LED3)") (class "Default")
      (node (ref "R41") (pin "1") (pinfunction "1_1") (pintype "passive"))
      (node (ref "U5") (pin "9") (pinfunction "LED3_9") (pintype "passive"))
    )
    (net (code "59") (name "Net-(U5-LED4)") (class "Default")
      (node (ref "R43") (pin "1") (pinfunction "1_1") (pintype "passive"))
      (node (ref "U5") (pin "10") (pinfunction "LED4_10") (pintype "passive"))
    )
    (net (code "60") (name "Net-(U5-LED5)") (class "Default")
      (node (ref "R44") (pin "1") (pinfunction "1_1") (pintype "passive"))
      (node (ref "U5") (pin "11") (pinfunction "LED5_11") (pintype "passive"))
    )
    (net (code "61") (name "Net-(U5-LED6)") (class "Default")
      (node (ref "R45") (pin "1") (pinfunction "1_1") (pintype "passive"))
      (node (ref "U5") (pin "12") (pinfunction "LED6_12") (pintype "passive"))
    )
    (net (code "62") (name "Net-(U5-LED7)") (class "Default")
      (node (ref "R46") (pin "1") (pinfunction "1_1") (pintype "passive"))
      (node (ref "U5") (pin "13") (pinfunction "LED7_13") (pintype "passive"))
    )
    (net (code "63") (name "unconnected-(C11-Pad2)") (class "Default")
      (node (ref "C11") (pin "2") (pinfunction "2_2") (pintype "passive"))
    )
    (net (code "64") (name "unconnected-(C14-Pad2)") (class "Default")
      (node (ref "C14") (pin "2") (pinfunction "2_2") (pintype "passive"))
    )
    (net (code "65") (name "unconnected-(U5-LED8-Pad15)") (class "Default")
      (node (ref "U5") (pin "15") (pinfunction "LED8_15") (pintype "passive"))
    )
    (net (code "66") (name "unconnected-(U5-LED9-Pad16)") (class "Default")
      (node (ref "U5") (pin "16") (pinfunction "LED9_16") (pintype "passive"))
    )
    (net (code "67") (name "unconnected-(U5-LED10-Pad17)") (class "Default")
      (node (ref "U5") (pin "17") (pinfunction "LED10_17") (pintype "passive"))
    )
    (net (code "68") (name "unconnected-(U5-LED11-Pad18)") (class "Default")
      (node (ref "U5") (pin "18") (pinfunction "LED11_18") (pintype "passive"))
    )
    (net (code "69") (name "unconnected-(U5-LED12-Pad19)") (class "Default")
      (node (ref "U5") (pin "19") (pinfunction "LED12_19") (pintype "passive"))
    )
    (net (code "70") (name "unconnected-(U5-LED13-Pad20)") (class "Default")
      (node (ref "U5") (pin "20") (pinfunction "LED13_20") (pintype "passive"))
    )
    (net (code "71") (name "unconnected-(U5-LED14-Pad21)") (class "Default")
      (node (ref "U5") (pin "21") (pinfunction "LED14_21") (pintype "passive"))
    )
    (net (code "72") (name "unconnected-(U5-LED15-Pad22)") (class "Default")
      (node (ref "U5") (pin "22") (pinfunction "LED15_22") (pintype "passive"))
    )
    (net (code "73") (name "unconnected-(U6-~{INT}-Pad13)") (class "Default")
      (node (ref "U6") (pin "13") (pinfunction "~{INT}_13") (pintype "open_collector+no_connect"))
    )
    (net (code "74") (name "unconnected-(U7-EN-Pad5)") (class "Default")
      (node (ref "U7") (pin "5") (pinfunction "EN_5") (pintype "passive"))
    )
  )
)
